# Sheet2.net
KiCad netlist of a schematic drawn in Altium Designer
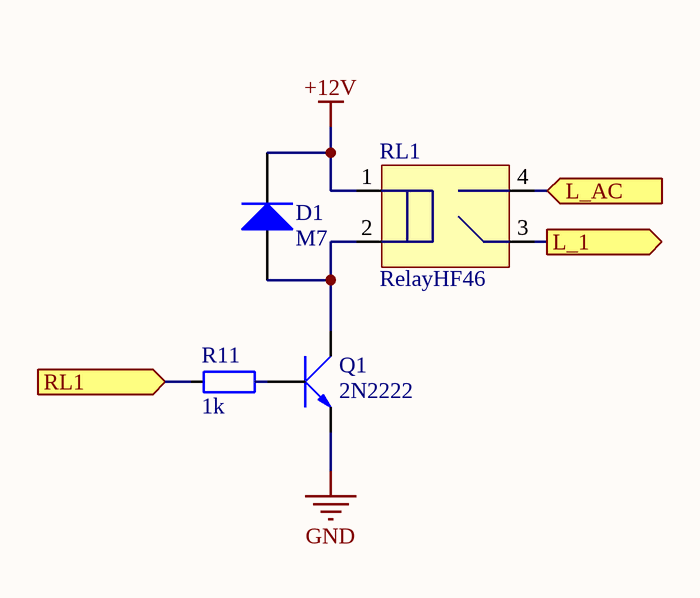
[diagram p0: Sheet2.SchDoc]

(export (version "E")
  (design (tool "Eeschema 10.0.6"))
  (components
    (comp (ref "D1")
      (value "M7")
      (footprint "DIODE SMA")
      (description "Dán")
      (libsource (lib "Altium_Lib_by_KhueNguyenCreator") (part "Diode M7 ( 4007 )"))
    )
    (comp (ref "Q1")
      (value "2N2222")
      (footprint "SOT23")
      (description "NPN transistor")
      (libsource (lib "Altium_Lib_by_KhueNguyenCreator") (part "C1815 HF SMD"))
    )
    (comp (ref "R11")
      (value "1k")
      (footprint "RES-SMD-0805")
      (description "Resistor")
      (fields
        (field (name "MANUFACTURER") "Generic Components")
        (field (name "PUBLISHER") "Altium Hobart Technology Centre")
      )
      (libsource (lib "My Library") (part "Resistor - SMD"))
    )
    (comp (ref "RL1")
      (value "RelayHF46")
      (footprint "Relay 4 chan HF46F")
      (description "Relay 4 chan HF46F")
      (libsource (lib "Altium_Lib_by_KhueNguyenCreator") (part "Relay 4 chan HF46F"))
    )
  )
  (nets
    (net (code "1") (name "+12V") (class "Default")
      (node (ref "D1") (pin "2") (pinfunction "K_2") (pintype "passive"))
      (node (ref "RL1") (pin "1") (pintype "passive"))
    )
    (net (code "2") (name "/L_1") (class "Default")
      (node (ref "RL1") (pin "3") (pinfunction "AC/DC_3") (pintype "passive"))
    )
    (net (code "3") (name "/L_AC") (class "Default")
      (node (ref "RL1") (pin "4") (pinfunction "AC/DC_4") (pintype "passive"))
    )
    (net (code "4") (name "/RL1") (class "Default")
      (node (ref "R11") (pin "1") (pinfunction "1_1") (pintype "passive"))
    )
    (net (code "5") (name "GND") (class "Default")
      (node (ref "Q1") (pin "2") (pinfunction "E_2") (pintype "passive"))
    )
    (net (code "6") (name "Net-(D1-A)") (class "Default")
      (node (ref "D1") (pin "1") (pinfunction "A_1") (pintype "passive"))
      (node (ref "Q1") (pin "3") (pinfunction "C_3") (pintype "passive"))
      (node (ref "RL1") (pin "2") (pintype "passive"))
    )
    (net (code "7") (name "Net-(Q1-B)") (class "Default")
      (node (ref "Q1") (pin "1") (pinfunction "B_1") (pintype "passive"))
      (node (ref "R11") (pin "2") (pinfunction "2_2") (pintype "passive"))
    )
  )
)
